# 1.net
KiCad netlist of a schematic drawn in Altium Designer
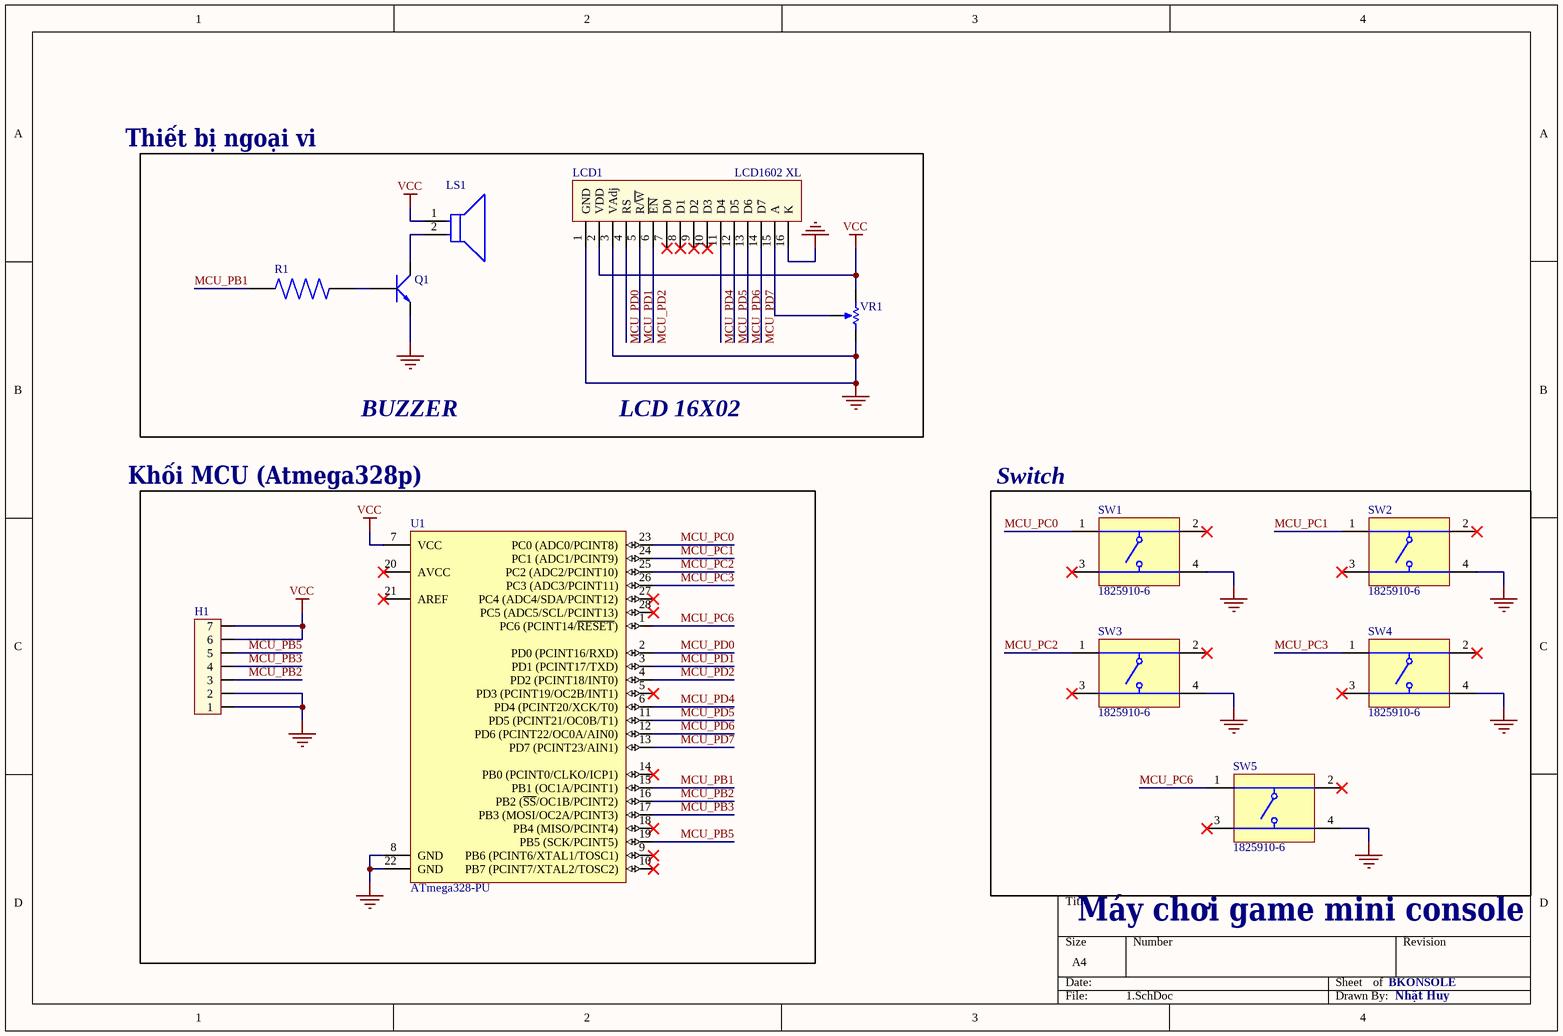
[diagram p0: 1.SchDoc]

(export (version "E")
  (design (tool "Eeschema 10.0.6"))
  (components
    (comp (ref "H1")
      (value "Header 7P 2.54 Duc Thang")
      (footprint "XH2.54M-7")
      (description "Cắm")
      (libsource (lib "Altium_Lib_by_KhueNguyenCreator") (part "Header 7P 2.54 Duc Thang"))
    )
    (comp (ref "LCD1")
      (value "LCD1602 XL")
      (footprint "LCD1602")
      (description "LCD 1602 Xanh Lá")
      (libsource (lib "Altium_Lib_by_KhueNguyenCreator") (part "LCD1602 XL"))
    )
    (comp (ref "LS1")
      (value "SD1614TT-A5ME")
      (footprint "FP-SD1614TT-A5ME-MFG")
      (description "BUZZER MAGNETIC 5V 80DB 2048HZ 1")
      (libsource (lib "Altium Content Vault") (part "1973c4b650225fd2ddacaff6b763965"))
    )
    (comp (ref "Q1")
      (value "C1815")
      (footprint "TO92")
      (description "NPN transistor")
      (libsource (lib "Altium_Lib_by_KhueNguyenCreator") (part "C1815"))
    )
    (comp (ref "R1")
      (value "MFR-25FBF52-1K")
      (footprint "RESAD1100W55L680D260")
      (description "1.07 kOhms Â±1% 0.25W, 1/4W Through Hole Resistor Axial - Metal Film")
      (fields (field (name "MF") "Yageo"))
      (libsource (lib "MFR-25FBF52-1K") (part "MFR-25FBF52-1K"))
    )
    (comp (ref "SW1")
      (value "1825910-6")
      (footprint "TECO-1825910-6_V")
      (description "Tact Switch, SPST-NO, 0.05 A, -35 to 85 degC, 4-Pin THD, RoHS, Bulk")
      (fields (field (name "MANUFACTURER") "TE Connectivity"))
      (libsource (lib "Altium Content Vault") (part "SW-SPST-4_A"))
    )
    (comp (ref "SW2")
      (value "1825910-6")
      (footprint "TECO-1825910-6_V")
      (description "Tact Switch, SPST-NO, 0.05 A, -35 to 85 degC, 4-Pin THD, RoHS, Bulk")
      (fields (field (name "MANUFACTURER") "TE Connectivity"))
      (libsource (lib "Altium Content Vault") (part "SW-SPST-4_A"))
    )
    (comp (ref "SW3")
      (value "1825910-6")
      (footprint "TECO-1825910-6_V")
      (description "Tact Switch, SPST-NO, 0.05 A, -35 to 85 degC, 4-Pin THD, RoHS, Bulk")
      (fields (field (name "MANUFACTURER") "TE Connectivity"))
      (libsource (lib "Altium Content Vault") (part "SW-SPST-4_A"))
    )
    (comp (ref "SW4")
      (value "1825910-6")
      (footprint "TECO-1825910-6_V")
      (description "Tact Switch, SPST-NO, 0.05 A, -35 to 85 degC, 4-Pin THD, RoHS, Bulk")
      (fields (field (name "MANUFACTURER") "TE Connectivity"))
      (libsource (lib "Altium Content Vault") (part "SW-SPST-4_A"))
    )
    (comp (ref "SW5")
      (value "1825910-6")
      (footprint "TECO-1825910-6_V")
      (description "Tact Switch, SPST-NO, 0.05 A, -35 to 85 degC, 4-Pin THD, RoHS, Bulk")
      (fields (field (name "MANUFACTURER") "TE Connectivity"))
      (libsource (lib "Altium Content Vault") (part "SW-SPST-4_A"))
    )
    (comp (ref "U1")
      (value "ATmega328-PU")
      (footprint "28P3")
      (libsource (lib "Altium Content Vault") (part "MC-8B-ATM48-IL28"))
    )
    (comp (ref "VR1")
      (value "3006P-1-201ZLF")
      (footprint "BOUR-3006P-3_V")
      (description "Trimming Potentiometer, 200 Ohm +/- 10%, -55 to 125 degC, 3-Pin 19.05 x 4.83 x 6.6 mm THD, RoHS")
      (fields (field (name "MANUFACTURER") "Bourns"))
      (libsource (lib "Altium Content Vault") (part "BOUR-3006P-3"))
    )
  )
  (nets
    (net (code "1") (name "/MCU_PB1") (class "Default")
      (node (ref "R1") (pin "1") (pinfunction "1_1") (pintype "passive"))
      (node (ref "U1") (pin "15") (pinfunction "PB1_(OC1A/PCINT1)_15") (pintype "bidirectional"))
    )
    (net (code "2") (name "/MCU_PB2") (class "Default")
      (node (ref "H1") (pin "3") (pinfunction "3_3") (pintype "passive"))
      (node (ref "U1") (pin "16") (pinfunction "PB2_(~{SS}/OC1B/PCINT2)_16") (pintype "bidirectional"))
    )
    (net (code "3") (name "/MCU_PB3") (class "Default")
      (node (ref "H1") (pin "4") (pinfunction "4_4") (pintype "passive"))
      (node (ref "U1") (pin "17") (pinfunction "PB3_(MOSI/OC2A/PCINT3)_17") (pintype "bidirectional"))
    )
    (net (code "4") (name "/MCU_PB5") (class "Default")
      (node (ref "H1") (pin "5") (pinfunction "5_5") (pintype "passive"))
      (node (ref "U1") (pin "19") (pinfunction "PB5_(SCK/PCINT5)_19") (pintype "bidirectional"))
    )
    (net (code "5") (name "/MCU_PC0") (class "Default")
      (node (ref "SW1") (pin "1") (pinfunction "1_1") (pintype "passive"))
      (node (ref "U1") (pin "23") (pinfunction "PC0_(ADC0/PCINT8)_23") (pintype "bidirectional"))
    )
    (net (code "6") (name "/MCU_PC1") (class "Default")
      (node (ref "SW2") (pin "1") (pinfunction "1_1") (pintype "passive"))
      (node (ref "U1") (pin "24") (pinfunction "PC1_(ADC1/PCINT9)_24") (pintype "bidirectional"))
    )
    (net (code "7") (name "/MCU_PC2") (class "Default")
      (node (ref "SW3") (pin "1") (pinfunction "1_1") (pintype "passive"))
      (node (ref "U1") (pin "25") (pinfunction "PC2_(ADC2/PCINT10)_25") (pintype "bidirectional"))
    )
    (net (code "8") (name "/MCU_PC3") (class "Default")
      (node (ref "SW4") (pin "1") (pinfunction "1_1") (pintype "passive"))
      (node (ref "U1") (pin "26") (pinfunction "PC3_(ADC3/PCINT11)_26") (pintype "bidirectional"))
    )
    (net (code "9") (name "/MCU_PC6") (class "Default")
      (node (ref "SW5") (pin "1") (pinfunction "1_1") (pintype "passive"))
      (node (ref "U1") (pin "1") (pinfunction "PC6_(PCINT14/~{RESET})_1") (pintype "bidirectional"))
    )
    (net (code "10") (name "/MCU_PD0") (class "Default")
      (node (ref "LCD1") (pin "4") (pinfunction "RS_4") (pintype "passive"))
      (node (ref "U1") (pin "2") (pinfunction "PD0_(PCINT16/RXD)_2") (pintype "bidirectional"))
    )
    (net (code "11") (name "/MCU_PD1") (class "Default")
      (node (ref "LCD1") (pin "5") (pinfunction "R/~{W}_5") (pintype "passive"))
      (node (ref "U1") (pin "3") (pinfunction "PD1_(PCINT17/TXD)_3") (pintype "bidirectional"))
    )
    (net (code "12") (name "/MCU_PD2") (class "Default")
      (node (ref "LCD1") (pin "6") (pinfunction "~{EN}_6") (pintype "passive"))
      (node (ref "U1") (pin "4") (pinfunction "PD2_(PCINT18/INT0)_4") (pintype "bidirectional"))
    )
    (net (code "13") (name "/MCU_PD4") (class "Default")
      (node (ref "LCD1") (pin "11") (pinfunction "D4_11") (pintype "passive"))
      (node (ref "U1") (pin "6") (pinfunction "PD4_(PCINT20/XCK/T0)_6") (pintype "bidirectional"))
    )
    (net (code "14") (name "/MCU_PD5") (class "Default")
      (node (ref "LCD1") (pin "12") (pinfunction "D5_12") (pintype "passive"))
      (node (ref "U1") (pin "11") (pinfunction "PD5_(PCINT21/OC0B/T1)_11") (pintype "bidirectional"))
    )
    (net (code "15") (name "/MCU_PD6") (class "Default")
      (node (ref "LCD1") (pin "13") (pinfunction "D6_13") (pintype "passive"))
      (node (ref "U1") (pin "12") (pinfunction "PD6_(PCINT22/OC0A/AIN0)_12") (pintype "bidirectional"))
    )
    (net (code "16") (name "/MCU_PD7") (class "Default")
      (node (ref "LCD1") (pin "14") (pinfunction "D7_14") (pintype "passive"))
      (node (ref "U1") (pin "13") (pinfunction "PD7_(PCINT23/AIN1)_13") (pintype "bidirectional"))
    )
    (net (code "17") (name "GND") (class "Default")
      (node (ref "H1") (pin "1") (pinfunction "1_1") (pintype "passive"))
      (node (ref "H1") (pin "2") (pinfunction "2_2") (pintype "passive"))
      (node (ref "LCD1") (pin "1") (pinfunction "GND_1") (pintype "passive"))
      (node (ref "LCD1") (pin "16") (pinfunction "K_16") (pintype "passive"))
      (node (ref "LCD1") (pin "3") (pinfunction "VAdj_3") (pintype "passive"))
      (node (ref "Q1") (pin "1") (pinfunction "E_1") (pintype "passive"))
      (node (ref "SW1") (pin "4") (pinfunction "4_4") (pintype "passive"))
      (node (ref "SW2") (pin "4") (pinfunction "4_4") (pintype "passive"))
      (node (ref "SW3") (pin "4") (pinfunction "4_4") (pintype "passive"))
      (node (ref "SW4") (pin "4") (pinfunction "4_4") (pintype "passive"))
      (node (ref "SW5") (pin "4") (pinfunction "4_4") (pintype "passive"))
      (node (ref "U1") (pin "22") (pinfunction "GND_22") (pintype "power_in"))
      (node (ref "U1") (pin "8") (pinfunction "GND_8") (pintype "power_in"))
      (node (ref "VR1") (pin "1") (pinfunction "CCW_1") (pintype "passive"))
    )
    (net (code "18") (name "Net-(LCD1-A)") (class "Default")
      (node (ref "LCD1") (pin "15") (pinfunction "A_15") (pintype "passive"))
      (node (ref "VR1") (pin "2") (pinfunction "WIPER_2") (pintype "passive"))
    )
    (net (code "19") (name "Net-(LS1-A)") (class "Default")
      (node (ref "LS1") (pin "2") (pinfunction "A_2") (pintype "passive"))
      (node (ref "Q1") (pin "2") (pinfunction "C_2") (pintype "passive"))
    )
    (net (code "20") (name "Net-(Q1-B)") (class "Default")
      (node (ref "Q1") (pin "3") (pinfunction "B_3") (pintype "passive"))
      (node (ref "R1") (pin "2") (pinfunction "2_2") (pintype "passive"))
    )
    (net (code "21") (name "VCC") (class "Default")
      (node (ref "H1") (pin "6") (pinfunction "6_6") (pintype "passive"))
      (node (ref "H1") (pin "7") (pinfunction "7_7") (pintype "passive"))
      (node (ref "LCD1") (pin "2") (pinfunction "VDD_2") (pintype "passive"))
      (node (ref "LS1") (pin "1") (pinfunction "C_1") (pintype "passive"))
      (node (ref "U1") (pin "7") (pinfunction "VCC_7") (pintype "power_in"))
      (node (ref "VR1") (pin "3") (pinfunction "CW_3") (pintype "passive"))
    )
    (net (code "22") (name "unconnected-(LCD1-D0-Pad7)") (class "Default")
      (node (ref "LCD1") (pin "7") (pinfunction "D0_7") (pintype "passive+no_connect"))
    )
    (net (code "23") (name "unconnected-(LCD1-D1-Pad8)") (class "Default")
      (node (ref "LCD1") (pin "8") (pinfunction "D1_8") (pintype "passive+no_connect"))
    )
    (net (code "24") (name "unconnected-(LCD1-D2-Pad9)") (class "Default")
      (node (ref "LCD1") (pin "9") (pinfunction "D2_9") (pintype "passive+no_connect"))
    )
    (net (code "25") (name "unconnected-(LCD1-D3-Pad10)") (class "Default")
      (node (ref "LCD1") (pin "10") (pinfunction "D3_10") (pintype "passive+no_connect"))
    )
    (net (code "26") (name "unconnected-(SW1-Pad2)") (class "Default")
      (node (ref "SW1") (pin "2") (pinfunction "2_2") (pintype "passive+no_connect"))
    )
    (net (code "27") (name "unconnected-(SW1-Pad3)") (class "Default")
      (node (ref "SW1") (pin "3") (pinfunction "3_3") (pintype "passive+no_connect"))
    )
    (net (code "28") (name "unconnected-(SW2-Pad2)") (class "Default")
      (node (ref "SW2") (pin "2") (pinfunction "2_2") (pintype "passive+no_connect"))
    )
    (net (code "29") (name "unconnected-(SW2-Pad3)") (class "Default")
      (node (ref "SW2") (pin "3") (pinfunction "3_3") (pintype "passive+no_connect"))
    )
    (net (code "30") (name "unconnected-(SW3-Pad2)") (class "Default")
      (node (ref "SW3") (pin "2") (pinfunction "2_2") (pintype "passive+no_connect"))
    )
    (net (code "31") (name "unconnected-(SW3-Pad3)") (class "Default")
      (node (ref "SW3") (pin "3") (pinfunction "3_3") (pintype "passive+no_connect"))
    )
    (net (code "32") (name "unconnected-(SW4-Pad2)") (class "Default")
      (node (ref "SW4") (pin "2") (pinfunction "2_2") (pintype "passive+no_connect"))
    )
    (net (code "33") (name "unconnected-(SW4-Pad3)") (class "Default")
      (node (ref "SW4") (pin "3") (pinfunction "3_3") (pintype "passive+no_connect"))
    )
    (net (code "34") (name "unconnected-(SW5-Pad2)") (class "Default")
      (node (ref "SW5") (pin "2") (pinfunction "2_2") (pintype "passive+no_connect"))
    )
    (net (code "35") (name "unconnected-(SW5-Pad3)") (class "Default")
      (node (ref "SW5") (pin "3") (pinfunction "3_3") (pintype "passive+no_connect"))
    )
    (net (code "36") (name "unconnected-(U1-AREF-Pad21)") (class "Default")
      (node (ref "U1") (pin "21") (pinfunction "AREF_21") (pintype "power_in+no_connect"))
    )
    (net (code "37") (name "unconnected-(U1-AVCC-Pad20)") (class "Default")
      (node (ref "U1") (pin "20") (pinfunction "AVCC_20") (pintype "power_in+no_connect"))
    )
    (net (code "38") (name "unconnected-(U1-PB0_(PCINT0{slash}CLKO{slash}ICP1)-Pad14)") (class "Default")
      (node (ref "U1") (pin "14") (pinfunction "PB0_(PCINT0/CLKO/ICP1)_14") (pintype "bidirectional+no_connect"))
    )
    (net (code "39") (name "unconnected-(U1-PB4_(MISO{slash}PCINT4)-Pad18)") (class "Default")
      (node (ref "U1") (pin "18") (pinfunction "PB4_(MISO/PCINT4)_18") (pintype "bidirectional+no_connect"))
    )
    (net (code "40") (name "unconnected-(U1-PB6_(PCINT6{slash}XTAL1{slash}TOSC1)-Pad9)") (class "Default")
      (node (ref "U1") (pin "9") (pinfunction "PB6_(PCINT6/XTAL1/TOSC1)_9") (pintype "bidirectional+no_connect"))
    )
    (net (code "41") (name "unconnected-(U1-PB7_(PCINT7{slash}XTAL2{slash}TOSC2)-Pad10)") (class "Default")
      (node (ref "U1") (pin "10") (pinfunction "PB7_(PCINT7/XTAL2/TOSC2)_10") (pintype "bidirectional+no_connect"))
    )
    (net (code "42") (name "unconnected-(U1-PC4_(ADC4{slash}SDA{slash}PCINT12)-Pad27)") (class "Default")
      (node (ref "U1") (pin "27") (pinfunction "PC4_(ADC4/SDA/PCINT12)_27") (pintype "bidirectional+no_connect"))
    )
    (net (code "43") (name "unconnected-(U1-PC5_(ADC5{slash}SCL{slash}PCINT13)-Pad28)") (class "Default")
      (node (ref "U1") (pin "28") (pinfunction "PC5_(ADC5/SCL/PCINT13)_28") (pintype "bidirectional+no_connect"))
    )
    (net (code "44") (name "unconnected-(U1-PD3_(PCINT19{slash}OC2B{slash}INT1)-Pad5)") (class "Default")
      (node (ref "U1") (pin "5") (pinfunction "PD3_(PCINT19/OC2B/INT1)_5") (pintype "bidirectional+no_connect"))
    )
  )
)
